# AD595_thermocouple_breakout_board-rev3.net
KiCad netlist of a schematic drawn in EAGLE
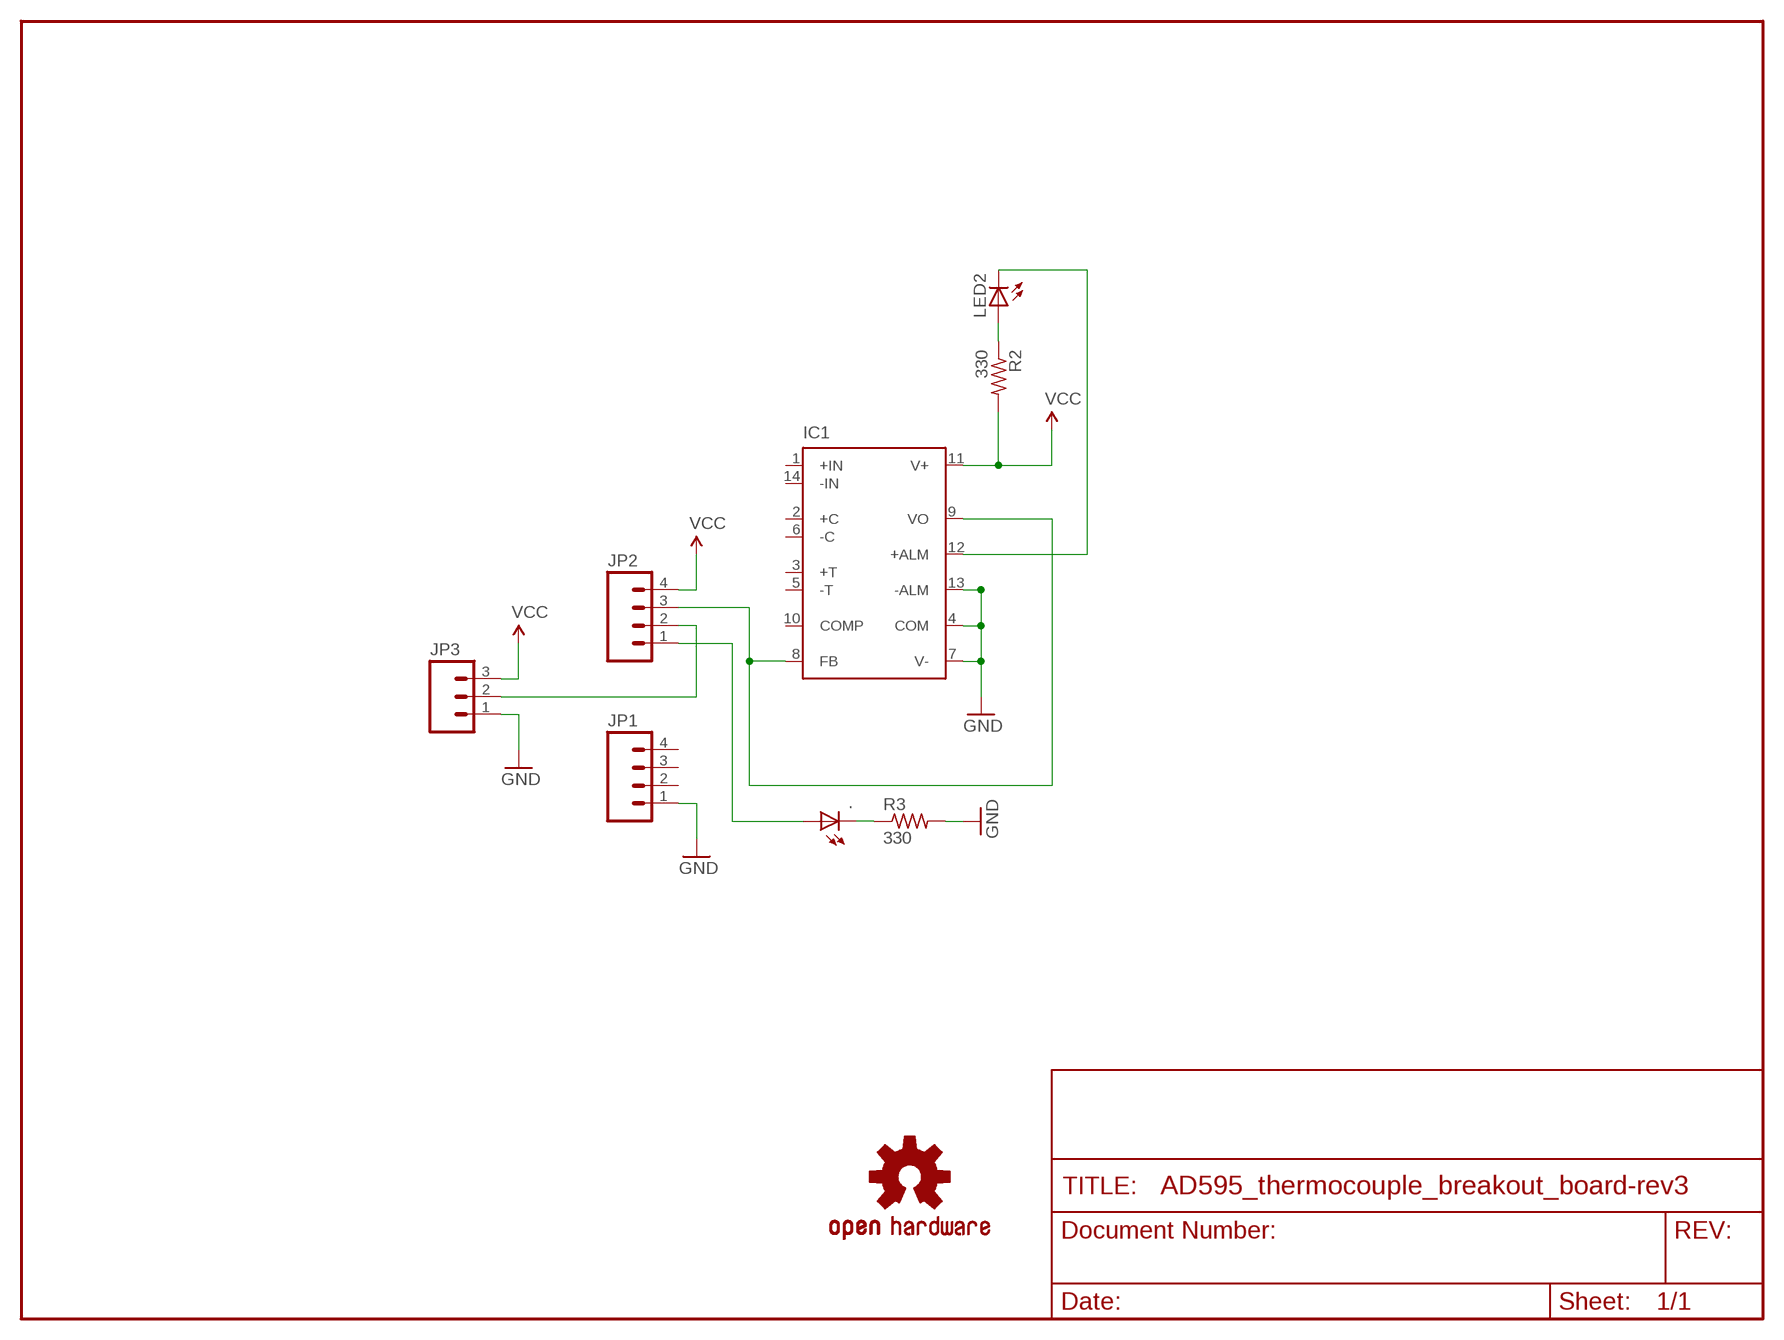
[diagram p0: schematic, sheet 1]

(export (version "E")
  (design (tool "Eeschema 10.0.6"))
  (components
    (comp (ref ".")
      (value "LED5MM")
      (footprint "eagle-import:LED5MM")
      (libsource (lib "eagle-import") (part "LED5MM"))
    )
    (comp (ref "IC1")
      (value "AD595")
      (footprint "eagle-import:DIL14")
      (libsource (lib "eagle-import") (part "AD595"))
    )
    (comp (ref "JP1")
      (value "M04LOCK")
      (footprint "eagle-import:1X04_LOCK")
      (libsource (lib "eagle-import") (part "M04LOCK"))
    )
    (comp (ref "JP2")
      (value "M04LOCK")
      (footprint "eagle-import:1X04_LOCK")
      (libsource (lib "eagle-import") (part "M04LOCK"))
    )
    (comp (ref "JP3")
      (value "M03SCREW_LOCK")
      (footprint "eagle-import:SCREWTERMINAL-3.5MM-3_LOCK.007S")
      (libsource (lib "eagle-import") (part "M03SCREW_LOCK"))
    )
    (comp (ref "LED2")
      (value "LED5MM")
      (footprint "eagle-import:LED5MM")
      (libsource (lib "eagle-import") (part "LED5MM"))
    )
    (comp (ref "R2")
      (value "330")
      (footprint "eagle-import:0207_7")
      (libsource (lib "eagle-import") (part "R-US_0207/7"))
    )
    (comp (ref "R3")
      (value "330")
      (footprint "eagle-import:0207_7")
      (libsource (lib "eagle-import") (part "R-US_0207/7"))
    )
    (comp (ref "U$1")
      (value "OSHW-LOGOS")
      (footprint "eagle-import:OSHW-LOGO-S")
      (libsource (lib "eagle-import") (part "OSHW-LOGOS"))
    )
  )
  (nets
    (net (code "1") (name "GND") (class "Default")
      (node (ref "IC1") (pin "13") (pinfunction "-ALM_13") (pintype "passive"))
      (node (ref "IC1") (pin "4") (pinfunction "COM_4") (pintype "power_in"))
      (node (ref "IC1") (pin "7") (pinfunction "V-_7") (pintype "power_in"))
      (node (ref "JP1") (pin "1") (pinfunction "1_1") (pintype "passive"))
      (node (ref "JP3") (pin "1") (pinfunction "1_1") (pintype "passive"))
      (node (ref "R3") (pin "2") (pinfunction "2_2") (pintype "passive"))
    )
    (net (code "2") (name "Net-(.-C)") (class "Default")
      (node (ref ".") (pin "K") (pinfunction "C_K") (pintype "passive"))
      (node (ref "R3") (pin "1") (pinfunction "1_1") (pintype "passive"))
    )
    (net (code "3") (name "Net-(.-PadA)") (class "Default")
      (node (ref ".") (pin "A") (pinfunction "A_A") (pintype "passive"))
      (node (ref "JP2") (pin "1") (pinfunction "1_1") (pintype "passive"))
    )
    (net (code "4") (name "Net-(IC1-+ALM)") (class "Default")
      (node (ref "IC1") (pin "12") (pinfunction "+ALM_12") (pintype "passive"))
      (node (ref "LED2") (pin "K") (pinfunction "C_K") (pintype "passive"))
    )
    (net (code "5") (name "Net-(IC1-FB)") (class "Default")
      (node (ref "IC1") (pin "8") (pinfunction "FB_8") (pintype "passive"))
      (node (ref "IC1") (pin "9") (pinfunction "VO_9") (pintype "output"))
      (node (ref "JP2") (pin "3") (pinfunction "3_3") (pintype "passive"))
    )
    (net (code "6") (name "Net-(JP2-Pad2)") (class "Default")
      (node (ref "JP2") (pin "2") (pinfunction "2_2") (pintype "passive"))
      (node (ref "JP3") (pin "2") (pinfunction "2_2") (pintype "passive"))
    )
    (net (code "7") (name "Net-(LED2-PadA)") (class "Default")
      (node (ref "LED2") (pin "A") (pinfunction "A_A") (pintype "passive"))
      (node (ref "R2") (pin "1") (pinfunction "1_1") (pintype "passive"))
    )
    (net (code "8") (name "VCC") (class "Default")
      (node (ref "IC1") (pin "11") (pinfunction "V+_11") (pintype "power_in"))
      (node (ref "JP2") (pin "4") (pinfunction "4_4") (pintype "passive"))
      (node (ref "JP3") (pin "3") (pinfunction "3_3") (pintype "passive"))
      (node (ref "R2") (pin "2") (pinfunction "2_2") (pintype "passive"))
    )
    (net (code "9") (name "unconnected-(IC1-+C-Pad2)") (class "Default")
      (node (ref "IC1") (pin "2") (pinfunction "+C_2") (pintype "input"))
    )
    (net (code "10") (name "unconnected-(IC1-+IN-Pad1)") (class "Default")
      (node (ref "IC1") (pin "1") (pinfunction "+IN_1") (pintype "input"))
    )
    (net (code "11") (name "unconnected-(IC1-+T-Pad3)") (class "Default")
      (node (ref "IC1") (pin "3") (pinfunction "+T_3") (pintype "passive"))
    )
    (net (code "12") (name "unconnected-(IC1--C-Pad6)") (class "Default")
      (node (ref "IC1") (pin "6") (pinfunction "-C_6") (pintype "input"))
    )
    (net (code "13") (name "unconnected-(IC1--IN-Pad14)") (class "Default")
      (node (ref "IC1") (pin "14") (pinfunction "-IN_14") (pintype "input"))
    )
    (net (code "14") (name "unconnected-(IC1--T-Pad5)") (class "Default")
      (node (ref "IC1") (pin "5") (pinfunction "-T_5") (pintype "passive"))
    )
    (net (code "15") (name "unconnected-(IC1-COMP-Pad10)") (class "Default")
      (node (ref "IC1") (pin "10") (pinfunction "COMP_10") (pintype "passive"))
    )
    (net (code "16") (name "unconnected-(JP1-Pad2)") (class "Default")
      (node (ref "JP1") (pin "2") (pinfunction "2_2") (pintype "passive"))
    )
    (net (code "17") (name "unconnected-(JP1-Pad3)") (class "Default")
      (node (ref "JP1") (pin "3") (pinfunction "3_3") (pintype "passive"))
    )
    (net (code "18") (name "unconnected-(JP1-Pad4)") (class "Default")
      (node (ref "JP1") (pin "4") (pinfunction "4_4") (pintype "passive"))
    )
  )
)
